# microz.net
KiCad netlist of a schematic drawn in Altium Designer
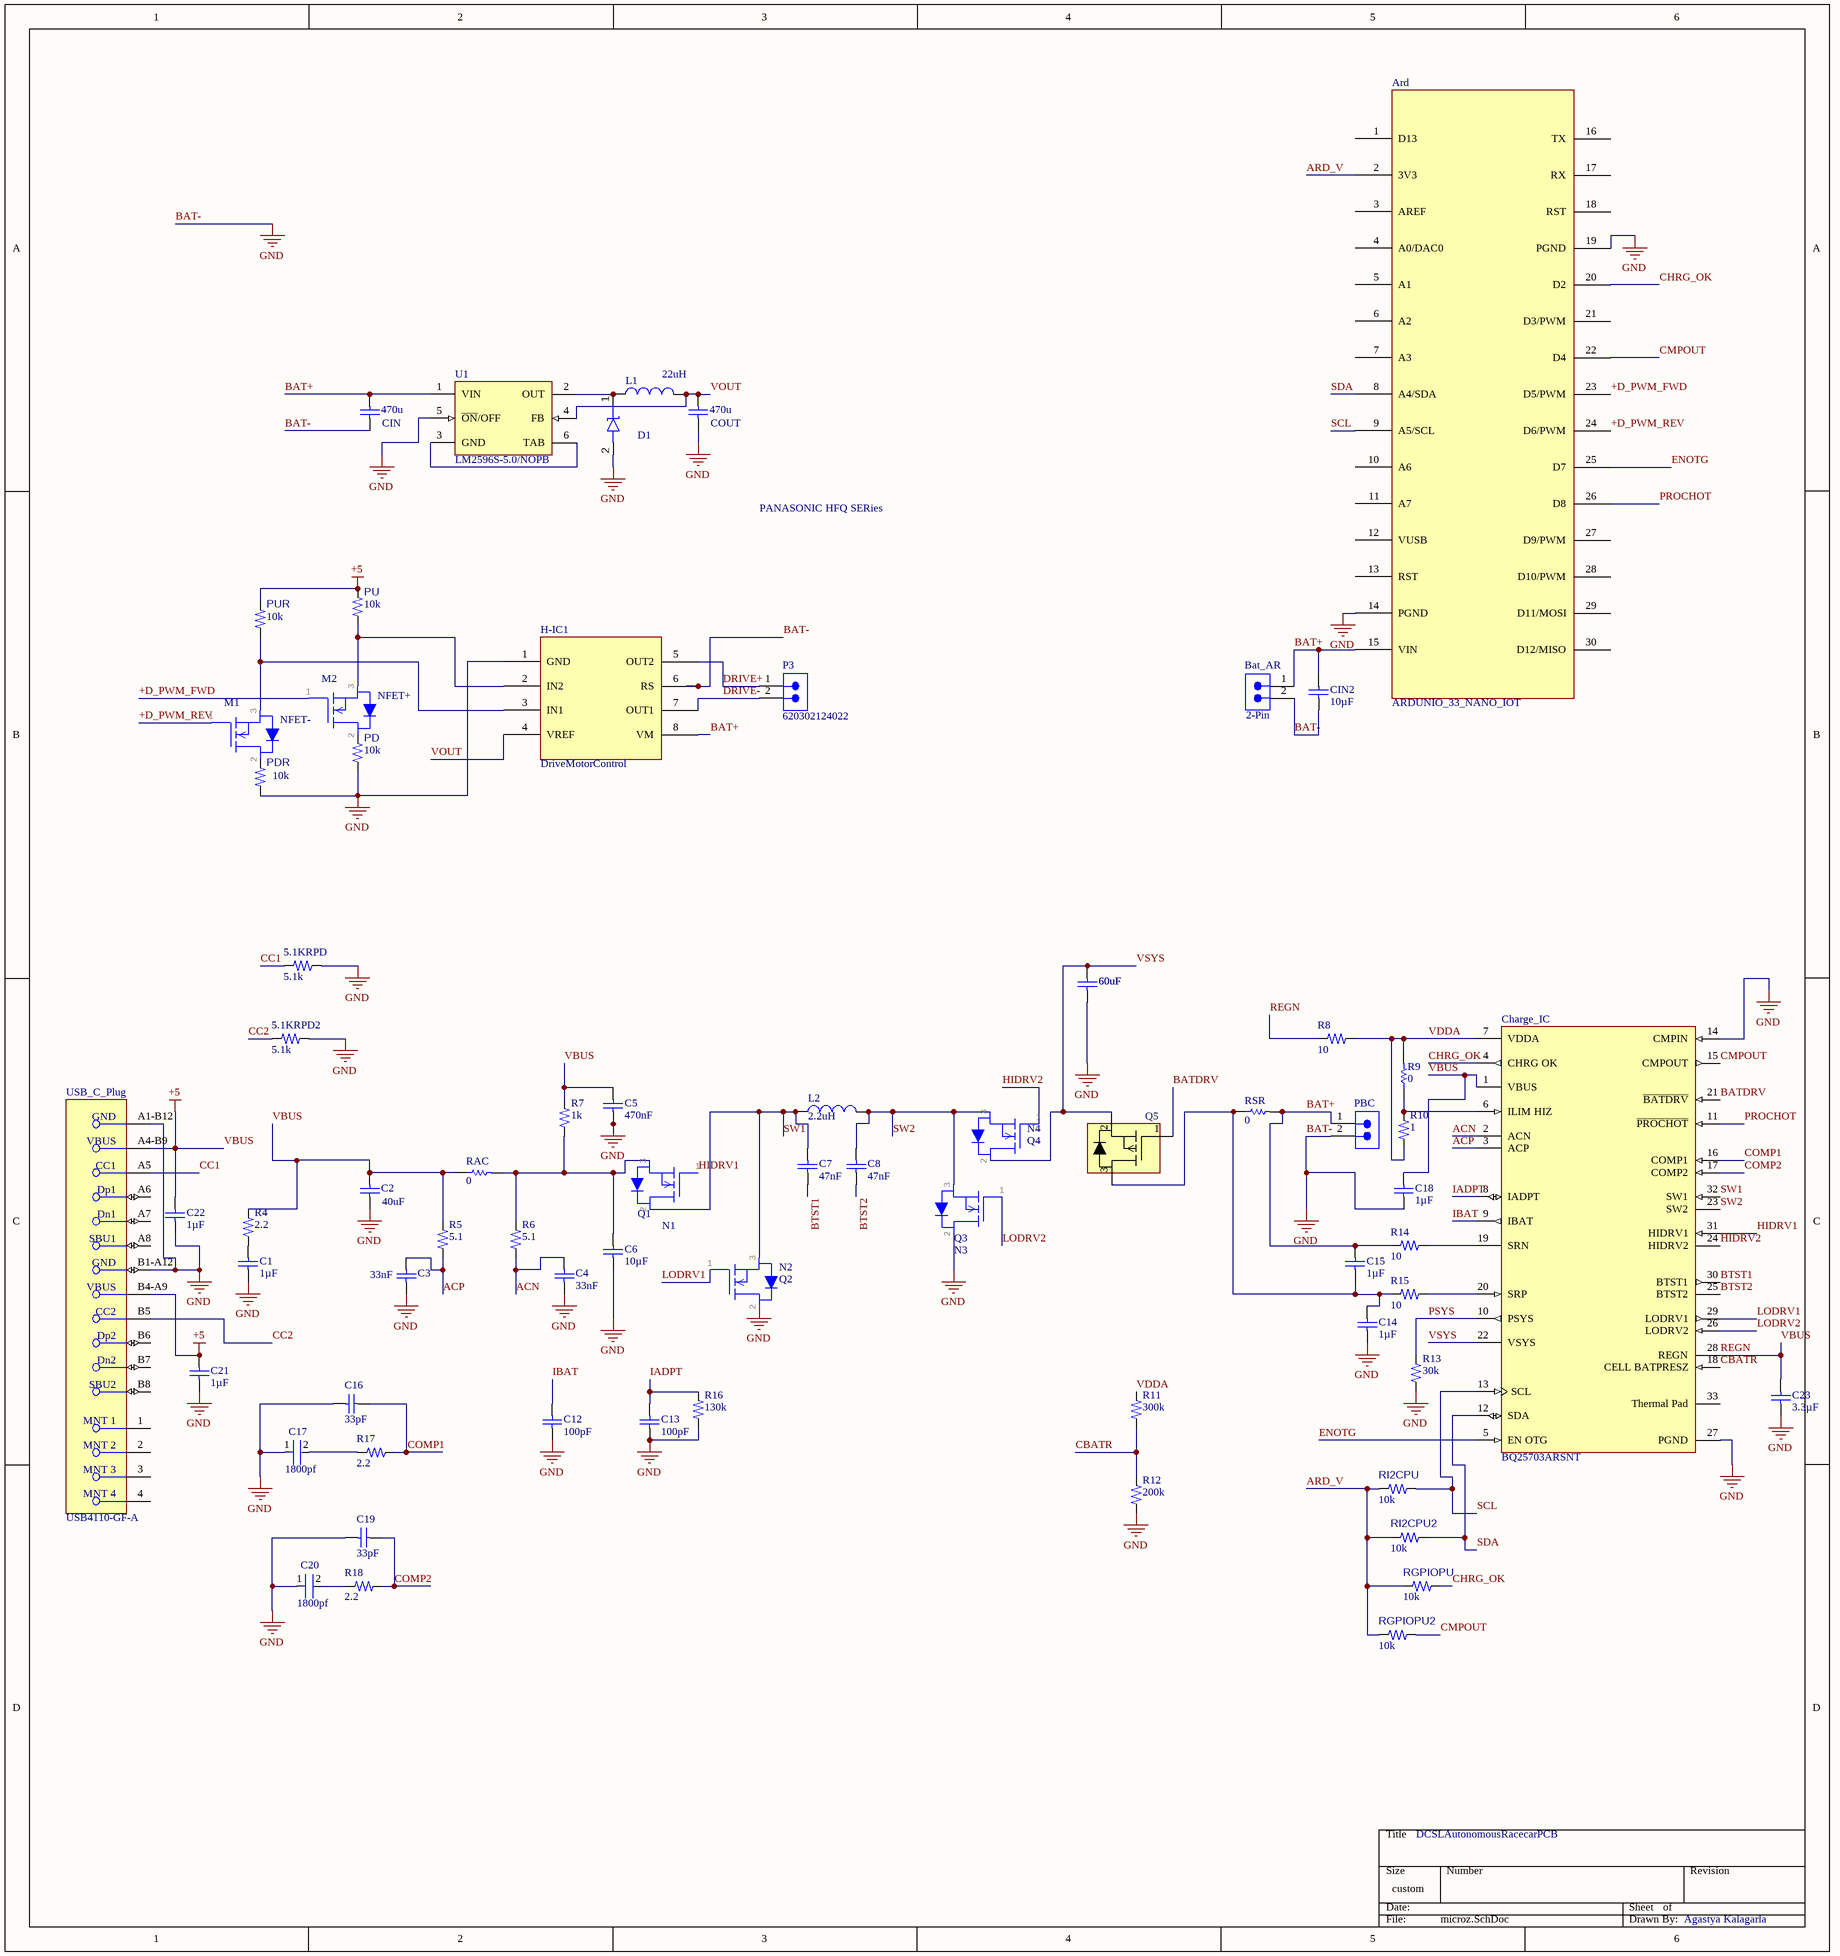
[diagram p0: microz.SchDoc]

(export (version "E")
  (design (tool "Eeschema 10.0.6"))
  (components
    (comp (ref "5.1KRPD")
      (value "5.1k")
      (footprint "RESC0603(1608)_L")
      (description "0603 (1608 Metric) 1/10 W 5K1 1 Precision Thick Film Chip Resistor")
      (fields (field (name "POWER") "100mW") (field (name "TOLERANCE") "0.1%"))
      (libsource (lib "Hytech Racing") (part "Resistor"))
    )
    (comp (ref "5.1KRPD2")
      (value "5.1k")
      (footprint "RESC0603(1608)_L")
      (description "0603 (1608 Metric) 1/10 W 5K1 1 Precision Thick Film Chip Resistor")
      (fields (field (name "POWER") "100mW") (field (name "TOLERANCE") "0.1%"))
      (libsource (lib "Hytech Racing") (part "Resistor"))
    )
    (comp (ref "60uF")
      (value "60uF")
      (footprint "RESC0603(1608)_L")
      (description "Imperial 0603 Capacitor")
      (fields (field (name "Comment") "0603-CAP"))
      (libsource (lib "Hytech Racing") (part "Capacitor-Ceramic"))
    )
    (comp (ref "Ard")
      (value "ARDUNIO_33_NANO_IOT")
      (footprint "Arduino33NanoIOT")
      (description "Arduino Nano IC for I2C Comms/Control")
      (libsource (lib "Schlib1") (part "ARDUNIO_33_NANO_IOT"))
    )
    (comp (ref "Bat_AR")
      (value "2-Pin")
      (footprint "620302124022")
      (libsource (lib "Altium Content Vault") (part "Header_Male_1R_02P"))
    )
    (comp (ref "C1")
      (value "1µF")
      (footprint "RESC0402(1005)_L")
      (description "Chip Capacitor, 1u 25V 0402 X7R")
      (fields (field (name "Comment") "Capacitor 1u"))
      (libsource (lib "Hytech Racing") (part "CAP-NP-2"))
    )
    (comp (ref "C2")
      (value "40uF")
      (footprint "RESC0603(1608)_L")
      (description "Imperial 0603 Capacitor")
      (fields (field (name "Comment") "0603-CAP"))
      (libsource (lib "Hytech Racing") (part "Capacitor-Ceramic"))
    )
    (comp (ref "C3")
      (value "33nF")
      (footprint "RESC0603(1608)_L")
      (description "Chip Capacitor, 33n 10V 0603 X7R")
      (fields (field (name "Comment") "Capacitor 33n"))
      (libsource (lib "Hytech Racing") (part "CAP-NP-2"))
    )
    (comp (ref "C4")
      (value "33nF")
      (footprint "RESC0603(1608)_L")
      (description "Chip Capacitor, 33n 10V 0603 X7R")
      (fields (field (name "Comment") "Capacitor 33n"))
      (libsource (lib "Hytech Racing") (part "CAP-NP-2"))
    )
    (comp (ref "C5")
      (value "470nF")
      (footprint "RESC0603(1608)_L")
      (description "Chip Capacitor, 470n 50V 0603 X7R")
      (fields (field (name "Comment") "Capacitor 470n"))
      (libsource (lib "Hytech Racing") (part "CAP-NP-2"))
    )
    (comp (ref "C6")
      (value "10µF")
      (footprint "RESC0805(2012)_L")
      (description "Chip Capacitor, 10u 25V 0805 X7R")
      (fields (field (name "Comment") "Capacitor 10u"))
      (libsource (lib "Hytech Racing") (part "CAP-NP-2"))
    )
    (comp (ref "C7")
      (value "47nF")
      (footprint "RESC0603(1608)_L")
      (description "Chip Capacitor, 47n 50V 0603 X7R")
      (fields (field (name "Comment") "Capacitor 47n"))
      (libsource (lib "Hytech Racing") (part "CAP-NP-2"))
    )
    (comp (ref "C8")
      (value "47nF")
      (footprint "RESC0603(1608)_L")
      (description "Chip Capacitor, 47n 50V 0603 X7R")
      (fields (field (name "Comment") "Capacitor 47n"))
      (libsource (lib "Hytech Racing") (part "CAP-NP-2"))
    )
    (comp (ref "C12")
      (value "100pF")
      (footprint "RESC0603(1608)_L")
      (description "Chip Capacitor, 100p 50V 0603 X7R")
      (fields (field (name "Comment") "Capacitor 100p"))
      (libsource (lib "Hytech Racing") (part "CAP-NP-2"))
    )
    (comp (ref "C13")
      (value "100pF")
      (footprint "RESC0603(1608)_L")
      (description "Chip Capacitor, 100p 50V 0603 X7R")
      (fields (field (name "Comment") "Capacitor 100p"))
      (libsource (lib "Hytech Racing") (part "CAP-NP-2"))
    )
    (comp (ref "C14")
      (value "1µF")
      (footprint "RESC0402(1005)_L")
      (description "Chip Capacitor, 1u 25V 0402 X7R")
      (fields (field (name "Comment") "Capacitor 1u"))
      (libsource (lib "Hytech Racing") (part "CAP-NP-2"))
    )
    (comp (ref "C15")
      (value "1µF")
      (footprint "RESC0402(1005)_L")
      (description "Chip Capacitor, 1u 25V 0402 X7R")
      (fields (field (name "Comment") "Capacitor 1u"))
      (libsource (lib "Hytech Racing") (part "CAP-NP-2"))
    )
    (comp (ref "C16")
      (value "33pF")
      (footprint "RESC0603(1608)_L")
      (description "Chip Capacitor, 33p 50V 0603 X7R")
      (fields (field (name "Comment") "Capacitor 33p"))
      (libsource (lib "Hytech Racing") (part "CAP-NP-2"))
    )
    (comp (ref "C17")
      (value "1800pf")
      (footprint "FP-GRM188-0_1-e0_2_0_5-IPC_A")
      (description "Chip Multilayer Ceramic Capacitors for General Purpose, 0603, 1800pF, C0G, 30ppm/°C, 5%, 50V")
      (fields (field (name "TOLERANCE") "5%") (field (name "VOLTAGE") "50V"))
      (libsource (lib "Altium Content Vault") (part "11868f565c42a9108669ba33697ecf6"))
    )
    (comp (ref "C18")
      (value "1µF")
      (footprint "RESC0402(1005)_L")
      (description "Chip Capacitor, 1u 25V 0402 X7R")
      (fields (field (name "Comment") "Capacitor 1u"))
      (libsource (lib "Hytech Racing") (part "CAP-NP-2"))
    )
    (comp (ref "C19")
      (value "33pF")
      (footprint "RESC0603(1608)_L")
      (description "Chip Capacitor, 33p 50V 0603 X7R")
      (fields (field (name "Comment") "Capacitor 33p"))
      (libsource (lib "Hytech Racing") (part "CAP-NP-2"))
    )
    (comp (ref "C20")
      (value "1800pf")
      (footprint "FP-GRM188-0_1-e0_2_0_5-IPC_A")
      (description "Chip Multilayer Ceramic Capacitors for General Purpose, 0603, 1800pF, C0G, 30ppm/°C, 5%, 50V")
      (fields (field (name "TOLERANCE") "5%") (field (name "VOLTAGE") "50V"))
      (libsource (lib "Altium Content Vault") (part "11868f565c42a9108669ba33697ecf6"))
    )
    (comp (ref "C21")
      (value "1µF")
      (footprint "RESC0402(1005)_L")
      (description "Chip Capacitor, 1u 25V 0402 X7R")
      (fields (field (name "Comment") "Capacitor 1u"))
      (libsource (lib "Hytech Racing") (part "CAP-NP-2"))
    )
    (comp (ref "C22")
      (value "1µF")
      (footprint "RESC0402(1005)_L")
      (description "Chip Capacitor, 1u 25V 0402 X7R")
      (fields (field (name "Comment") "Capacitor 1u"))
      (libsource (lib "Hytech Racing") (part "CAP-NP-2"))
    )
    (comp (ref "C23")
      (value "3.3µF")
      (footprint "RESC0603(1608)_L")
      (description "Chip Capacitor, 3u3 50V 0603 X7R")
      (fields (field (name "Comment") "Capacitor 3u3"))
      (libsource (lib "Hytech Racing") (part "CAP-NP-2"))
    )
    (comp (ref "Charge_IC")
      (value "BQ25703ARSNT")
      (footprint "FP-RSN0032B-MFG")
      (description "IC BATT MON MULTI-CHEM 32WQFN")
      (fields
        (field (name "OCTOPART") "https://octopart.com/bq25703arsnt-texas+instruments-81848930")
        (field (name "MANUFACTURER") "Texas Instruments")
      )
      (libsource (lib "Altium Content Vault") (part "15ddd9f6a7647243260becfffa45dc3"))
    )
    (comp (ref "CIN")
      (value "470u")
      (footprint "RESC0603(1608)_L")
      (description "Imperial 0603 Capacitor")
      (fields (field (name "Comment") "0603-CAP"))
      (libsource (lib "Hytech Racing") (part "Capacitor-Ceramic"))
    )
    (comp (ref "CIN2")
      (value "10µF")
      (footprint "RESC0805(2012)_L")
      (description "Chip Capacitor, 10u 50V 0805 X7R")
      (fields (field (name "Comment") "Capacitor 10u"))
      (libsource (lib "Hytech Racing") (part "CAP-NP-2"))
    )
    (comp (ref "COUT")
      (value "470u")
      (footprint "RESC0603(1608)_L")
      (description "Imperial 0603 Capacitor")
      (fields (field (name "Comment") "0603-CAP"))
      (libsource (lib "Hytech Racing") (part "Capacitor-Ceramic"))
    )
    (comp (ref "D1")
      (value "DIODE_SCHOTTKY_SOD-323")
      (footprint "SOD-323")
      (description "Schottky Diode with SOD-323 Footprint")
      (libsource (lib "Hytech Racing") (part "Schottky Diode"))
    )
    (comp (ref "H-IC1")
      (value "DriveMotorControl")
      (footprint "TB67H451FNG,EL")
      (description "H-Bridge IC")
      (libsource (lib "Schlib1") (part "DriveMotorControl"))
    )
    (comp (ref "L1")
      (value "22uH")
      (footprint "INDC3225X24N")
      (description "1210 Inductor")
      (libsource (lib "Hytech Racing") (part "IND_1210"))
    )
    (comp (ref "L2")
      (value "2.2uH")
      (footprint "INDC3225X24N")
      (description "1210 Inductor")
      (fields (field (name "Comment") "IND_1210"))
      (libsource (lib "Hytech Racing") (part "IND_1210"))
    )
    (comp (ref "N1")
      (value "Q1")
      (footprint "DPAK(2-7K1S)")
      (description "N Channel MOSFET, DPAK(2-7K1S) Footprint")
      (libsource (lib "Hytech Racing") (part "N Channel MOSFET"))
    )
    (comp (ref "N2")
      (value "Q2")
      (footprint "DPAK(2-7K1S)")
      (description "N Channel MOSFET, DPAK(2-7K1S) Footprint")
      (libsource (lib "Hytech Racing") (part "N Channel MOSFET"))
    )
    (comp (ref "N3")
      (value "Q3")
      (footprint "DPAK(2-7K1S)")
      (description "N Channel MOSFET, DPAK(2-7K1S) Footprint")
      (libsource (lib "Hytech Racing") (part "N Channel MOSFET"))
    )
    (comp (ref "N4")
      (value "Q4")
      (footprint "DPAK(2-7K1S)")
      (description "N Channel MOSFET, DPAK(2-7K1S) Footprint")
      (libsource (lib "Hytech Racing") (part "N Channel MOSFET"))
    )
    (comp (ref "NFET+")
      (value "M2")
      (footprint "DPAK(2-7K1S)")
      (description "N Channel MOSFET, DPAK(2-7K1S) Footprint")
      (libsource (lib "Hytech Racing") (part "N Channel MOSFET"))
    )
    (comp (ref "NFET-")
      (value "M1")
      (footprint "DPAK(2-7K1S)")
      (description "N Channel MOSFET, DPAK(2-7K1S) Footprint")
      (libsource (lib "Hytech Racing") (part "N Channel MOSFET"))
    )
    (comp (ref "P3")
      (value "620302124022")
      (footprint "620302124022")
      (libsource (lib "Altium Content Vault") (part "Header_Male_1R_02P"))
    )
    (comp (ref "PBC")
      (value "620302124022")
      (footprint "620302124022")
      (libsource (lib "Altium Content Vault") (part "Header_Male_1R_02P"))
    )
    (comp (ref "PD")
      (value "10k")
      (footprint "RESC0603(1608)_L")
      (description "0603 (1608 Metric) 1/10 W 10K 1 Precision Thick Film Chip Resistor")
      (fields (field (name "POWER") "100mW") (field (name "TOLERANCE") "0.1%"))
      (libsource (lib "Hytech Racing") (part "Resistor"))
    )
    (comp (ref "PDR")
      (value "10k")
      (footprint "RESC0603(1608)_L")
      (description "0603 (1608 Metric) 1/10 W 10K 1 Precision Thick Film Chip Resistor")
      (fields (field (name "POWER") "100mW") (field (name "TOLERANCE") "0.1%"))
      (libsource (lib "Hytech Racing") (part "Resistor"))
    )
    (comp (ref "PU")
      (value "10k")
      (footprint "RESC0603(1608)_L")
      (description "0603 (1608 Metric) 1/10 W 10K 1 Precision Thick Film Chip Resistor")
      (fields (field (name "POWER") "100mW") (field (name "TOLERANCE") "0.1%"))
      (libsource (lib "Hytech Racing") (part "Resistor"))
    )
    (comp (ref "PUR")
      (value "10k")
      (footprint "RESC0603(1608)_L")
      (description "0603 (1608 Metric) 1/10 W 10K 1 Precision Thick Film Chip Resistor")
      (fields (field (name "POWER") "100mW") (field (name "TOLERANCE") "0.1%"))
      (libsource (lib "Hytech Racing") (part "Resistor"))
    )
    (comp (ref "Q5")
      (value "DMP3056L-7")
      (footprint "SOT96P240X110-3N/SOT23-3")
      (description "P-MOSFET Enhancement Mode")
      (fields (field (name "MANUFACTURER") "Diodes Incorporated") (field (name "SOURCE") "LOGICFETS.SchLib"))
      (libsource (lib "Hytech Racing") (part "DMP3056L-7"))
    )
    (comp (ref "R4")
      (value "2.2")
      (footprint "RESC0603(1608)_L")
      (description "0603 (1608 Metric) 1/10 W 2R2 5 Thick Film Chip Resistor")
      (fields (field (name "POWER") "100mW") (field (name "TOLERANCE") "5%"))
      (libsource (lib "Hytech Racing") (part "Resistor"))
    )
    (comp (ref "R5")
      (value "5.1")
      (footprint "RESC0603(1608)_L")
      (description "0603 (1608 Metric) 1/10 W 5R1 5 Thick Film Chip Resistor")
      (fields (field (name "POWER") "100mW") (field (name "TOLERANCE") "5%"))
      (libsource (lib "Hytech Racing") (part "Resistor"))
    )
    (comp (ref "R6")
      (value "5.1")
      (footprint "RESC0603(1608)_L")
      (description "0603 (1608 Metric) 1/10 W 5R1 5 Thick Film Chip Resistor")
      (fields (field (name "POWER") "100mW") (field (name "TOLERANCE") "5%"))
      (libsource (lib "Hytech Racing") (part "Resistor"))
    )
    (comp (ref "R7")
      (value "1k")
      (footprint "RESC0603(1608)_L")
      (description "0603 (1608 Metric) 1/10 W 1K 1 Precision Thick Film Chip Resistor")
      (fields (field (name "TOLERANCE") "0.1%") (field (name "POWER") "100mW"))
      (libsource (lib "Hytech Racing") (part "Resistor"))
    )
    (comp (ref "R8")
      (value "10")
      (footprint "RESC0603(1608)_L")
      (description "0603 (1608 Metric) 1/10 W 10R 1 Precision Thick Film Chip Resistor")
      (fields (field (name "POWER") "100mW") (field (name "TOLERANCE") "0.1%"))
      (libsource (lib "Hytech Racing") (part "Resistor"))
    )
    (comp (ref "R9")
      (value "0")
      (footprint "RESC1005X40X25ML05T05")
      (description "Chip Resistor, 0 Ohm, 0.1 W, -55 to 155 degC, 0402 (1005 Metric)")
      (fields (field (name "TOLERANCE") "5%") (field (name "POWER") "100mW"))
      (libsource (lib "Hytech Racing") (part "RES-2"))
    )
    (comp (ref "R10")
      (value "1")
      (footprint "RESC0603(1608)_L")
      (description "0603 (1608 Metric) 1/10 W 1R 5 Thick Film Chip Resistor")
      (fields (field (name "POWER") "100mW") (field (name "TOLERANCE") "5%"))
      (libsource (lib "Hytech Racing") (part "Resistor"))
    )
    (comp (ref "R11")
      (value "300k")
      (footprint "RESC0603(1608)_L")
      (description "0603 (1608 Metric) 1/10 W 300K 1 Precision Thick Film Chip Resistor")
      (fields (field (name "POWER") "100mW") (field (name "TOLERANCE") "0.1%"))
      (libsource (lib "Hytech Racing") (part "Resistor"))
    )
    (comp (ref "R12")
      (value "200k")
      (footprint "RESC0603(1608)_L")
      (description "0603 (1608 Metric) 1/10 W 200K 1 Precision Thick Film Chip Resistor")
      (fields (field (name "TOLERANCE") "0.1%") (field (name "POWER") "100mW"))
      (libsource (lib "Hytech Racing") (part "Resistor"))
    )
    (comp (ref "R13")
      (value "30k")
      (footprint "RESC0603(1608)_L")
      (description "0603 (1608 Metric) 1/10 W 30K 1 Precision Thick Film Chip Resistor")
      (fields (field (name "TOLERANCE") "0.1%") (field (name "POWER") "100mW"))
      (libsource (lib "Hytech Racing") (part "Resistor"))
    )
    (comp (ref "R14")
      (value "10")
      (footprint "RESC0603(1608)_L")
      (description "0603 (1608 Metric) 1/10 W 10R 1 Precision Thick Film Chip Resistor")
      (fields (field (name "POWER") "100mW") (field (name "TOLERANCE") "0.1%"))
      (libsource (lib "Hytech Racing") (part "Resistor"))
    )
    (comp (ref "R15")
      (value "10")
      (footprint "RESC0603(1608)_L")
      (description "0603 (1608 Metric) 1/10 W 10R 1 Precision Thick Film Chip Resistor")
      (fields (field (name "POWER") "100mW") (field (name "TOLERANCE") "0.1%"))
      (libsource (lib "Hytech Racing") (part "Resistor"))
    )
    (comp (ref "R16")
      (value "130k")
      (footprint "RESC0603(1608)_L")
      (description "0603 (1608 Metric) 1/10 W 130K 1 Precision Thick Film Chip Resistor")
      (fields (field (name "POWER") "100mW") (field (name "TOLERANCE") "0.1%"))
      (libsource (lib "Hytech Racing") (part "Resistor"))
    )
    (comp (ref "R17")
      (value "2.2")
      (footprint "RESC0603(1608)_L")
      (description "0603 (1608 Metric) 1/10 W 2R2 5 Thick Film Chip Resistor")
      (fields (field (name "POWER") "100mW") (field (name "TOLERANCE") "5%"))
      (libsource (lib "") (part "Resistor_1"))
    )
    (comp (ref "R18")
      (value "2.2")
      (footprint "RESC0603(1608)_L")
      (description "0603 (1608 Metric) 1/10 W 2R2 5 Thick Film Chip Resistor")
      (fields (field (name "POWER") "100mW") (field (name "TOLERANCE") "5%"))
      (libsource (lib "") (part "Resistor_1"))
    )
    (comp (ref "RAC")
      (value "0")
      (footprint "RESC1005X40X25ML05T05")
      (description "Chip Resistor, 0 Ohm, 0.1 W, -55 to 155 degC, 0402 (1005 Metric)")
      (fields (field (name "TOLERANCE") "5%") (field (name "POWER") "100mW"))
      (libsource (lib "Hytech Racing") (part "RES-2"))
    )
    (comp (ref "RGPIOPU")
      (value "10k")
      (footprint "RESC0603(1608)_L")
      (description "0603 (1608 Metric) 1/10 W 10K 1 Precision Thick Film Chip Resistor")
      (fields (field (name "POWER") "100mW") (field (name "TOLERANCE") "0.1%"))
      (libsource (lib "Hytech Racing") (part "Resistor"))
    )
    (comp (ref "RGPIOPU2")
      (value "10k")
      (footprint "RESC0603(1608)_L")
      (description "0603 (1608 Metric) 1/10 W 10K 1 Precision Thick Film Chip Resistor")
      (fields (field (name "POWER") "100mW") (field (name "TOLERANCE") "0.1%"))
      (libsource (lib "Hytech Racing") (part "Resistor"))
    )
    (comp (ref "RI2CPU")
      (value "10k")
      (footprint "RESC0603(1608)_L")
      (description "0603 (1608 Metric) 1/10 W 10K 1 Precision Thick Film Chip Resistor")
      (fields (field (name "POWER") "100mW") (field (name "TOLERANCE") "0.1%"))
      (libsource (lib "Hytech Racing") (part "Resistor"))
    )
    (comp (ref "RI2CPU2")
      (value "10k")
      (footprint "RESC0603(1608)_L")
      (description "0603 (1608 Metric) 1/10 W 10K 1 Precision Thick Film Chip Resistor")
      (fields (field (name "POWER") "100mW") (field (name "TOLERANCE") "0.1%"))
      (libsource (lib "Hytech Racing") (part "Resistor"))
    )
    (comp (ref "RSR")
      (value "0")
      (footprint "RESC1005X40X25ML05T05")
      (description "Chip Resistor, 0 Ohm, 0.1 W, -55 to 155 degC, 0402 (1005 Metric)")
      (fields (field (name "TOLERANCE") "5%") (field (name "POWER") "100mW"))
      (libsource (lib "Hytech Racing") (part "RES-2"))
    )
    (comp (ref "U1")
      (value "LM2596S-5.0/NOPB")
      (footprint "KTT0005B_M")
      (description "SIMPLE SWITCHER® Power Converter 150 KHz 3A Step-Down Voltage Regulator, 5-pin TO-263, Pb-Free")
      (fields (field (name "MANUFACTURER") "Texas Instruments"))
      (libsource (lib "Altium Content Vault") (part "PM-REG-LM2575HVS-12"))
    )
    (comp (ref "USB_C_Plug")
      (value "USB4110-GF-A")
      (footprint "FP-USB4110-GF-A-MFG")
      (description "CONN USB 2.0 TYPE-C R/A SMT")
      (fields
        (field (name "OCTOPART") "https://octopart.com/usb4110-gf-a-gct-103941985")
        (field (name "MANUFACTURER") "GCT")
      )
      (libsource (lib "Altium Content Vault") (part "e23f2b38bb3c3f98e683ebab9ede730"))
    )
  )
  (nets
    (net (code "1") (name "+5") (class "Default")
      (node (ref "C18") (pin "2") (pinfunction "2_2") (pintype "passive"))
      (node (ref "C2") (pin "2") (pinfunction "2_2") (pintype "passive"))
      (node (ref "C21") (pin "2") (pinfunction "2_2") (pintype "passive"))
      (node (ref "C22") (pin "2") (pinfunction "2_2") (pintype "passive"))
      (node (ref "C23") (pin "2") (pinfunction "2_2") (pintype "passive"))
      (node (ref "C5") (pin "2") (pinfunction "2_2") (pintype "passive"))
      (node (ref "Charge_IC") (pin "1") (pinfunction "VBUS_1") (pintype "power_in"))
      (node (ref "Charge_IC") (pin "28") (pinfunction "REGN_28") (pintype "power_in"))
      (node (ref "PU") (pin "2") (pinfunction "2_2") (pintype "passive"))
      (node (ref "PUR") (pin "2") (pinfunction "2_2") (pintype "passive"))
      (node (ref "R4") (pin "2") (pinfunction "2_2") (pintype "passive"))
      (node (ref "R5") (pin "2") (pinfunction "2_2") (pintype "passive"))
      (node (ref "R7") (pin "2") (pinfunction "2_2") (pintype "passive"))
      (node (ref "R8") (pin "1") (pinfunction "1_1") (pintype "passive"))
      (node (ref "RAC") (pin "1") (pinfunction "1_1") (pintype "passive"))
      (node (ref "USB_C_Plug") (pin "A4-B9") (pinfunction "VBUS_A4-B9") (pintype "power_in"))
      (node (ref "USB_C_Plug") (pin "B4-A9") (pinfunction "VBUS_B4-A9") (pintype "power_in"))
    )
    (net (code "2") (name "/+D_PWM_FWD") (class "Default")
      (node (ref "Ard") (pin "23") (pinfunction "D5/PWM_23") (pintype "passive"))
      (node (ref "NFET+") (pin "1") (pinfunction "Gate_1") (pintype "passive"))
    )
    (net (code "3") (name "/+D_PWM_REV") (class "Default")
      (node (ref "Ard") (pin "24") (pinfunction "D6/PWM_24") (pintype "passive"))
      (node (ref "NFET-") (pin "1") (pinfunction "Gate_1") (pintype "passive"))
    )
    (net (code "4") (name "/ACN") (class "Default")
      (node (ref "C4") (pin "2") (pinfunction "2_2") (pintype "passive"))
      (node (ref "Charge_IC") (pin "2") (pinfunction "ACN_2") (pintype "power_in"))
      (node (ref "R6") (pin "1") (pinfunction "1_1") (pintype "passive"))
    )
    (net (code "5") (name "/ACP") (class "Default")
      (node (ref "C3") (pin "2") (pinfunction "2_2") (pintype "passive"))
      (node (ref "Charge_IC") (pin "3") (pinfunction "ACP_3") (pintype "power_in"))
      (node (ref "R5") (pin "1") (pinfunction "1_1") (pintype "passive"))
    )
    (net (code "6") (name "/ARD_V") (class "Default")
      (node (ref "Ard") (pin "2") (pinfunction "3V3_2") (pintype "passive"))
      (node (ref "RGPIOPU") (pin "1") (pinfunction "1_1") (pintype "passive"))
      (node (ref "RGPIOPU2") (pin "1") (pinfunction "1_1") (pintype "passive"))
      (node (ref "RI2CPU") (pin "1") (pinfunction "1_1") (pintype "passive"))
      (node (ref "RI2CPU2") (pin "1") (pinfunction "1_1") (pintype "passive"))
    )
    (net (code "7") (name "/BAT+") (class "Default")
      (node (ref "Ard") (pin "15") (pinfunction "VIN_15") (pintype "passive"))
      (node (ref "Bat_AR") (pin "1") (pinfunction "1_1") (pintype "passive"))
      (node (ref "C15") (pin "2") (pinfunction "2_2") (pintype "passive"))
      (node (ref "CIN") (pin "2") (pinfunction "2_2") (pintype "passive"))
      (node (ref "CIN2") (pin "2") (pinfunction "2_2") (pintype "passive"))
      (node (ref "H-IC1") (pin "8") (pinfunction "VM_8") (pintype "passive"))
      (node (ref "PBC") (pin "1") (pinfunction "1_1") (pintype "passive"))
      (node (ref "R14") (pin "1") (pinfunction "1_1") (pintype "passive"))
      (node (ref "RSR") (pin "2") (pinfunction "2_2") (pintype "passive"))
      (node (ref "U1") (pin "1") (pinfunction "VIN_1") (pintype "power_in"))
    )
    (net (code "8") (name "/BATDRV") (class "Default")
      (node (ref "Charge_IC") (pin "21") (pinfunction "~{BATDRV}_21") (pintype "input"))
      (node (ref "Q5") (pin "1") (pinfunction "G_1") (pintype "passive"))
    )
    (net (code "9") (name "/BTST1") (class "Default")
      (node (ref "C7") (pin "1") (pinfunction "1_1") (pintype "passive"))
      (node (ref "Charge_IC") (pin "30") (pinfunction "BTST1_30") (pintype "output"))
    )
    (net (code "10") (name "/BTST2") (class "Default")
      (node (ref "C8") (pin "1") (pinfunction "1_1") (pintype "passive"))
      (node (ref "Charge_IC") (pin "25") (pinfunction "BTST2_25") (pintype "power_in"))
    )
    (net (code "11") (name "/CBATR") (class "Default")
      (node (ref "Charge_IC") (pin "18") (pinfunction "CELL_BATPRESZ_18") (pintype "input"))
      (node (ref "R11") (pin "1") (pinfunction "1_1") (pintype "passive"))
      (node (ref "R12") (pin "2") (pinfunction "2_2") (pintype "passive"))
    )
    (net (code "12") (name "/CC1") (class "Default")
      (node (ref "5.1KRPD") (pin "1") (pinfunction "1_1") (pintype "passive"))
      (node (ref "USB_C_Plug") (pin "A5") (pinfunction "CC1_A5") (pintype "power_in"))
    )
    (net (code "13") (name "/CC2") (class "Default")
      (node (ref "5.1KRPD2") (pin "1") (pinfunction "1_1") (pintype "passive"))
      (node (ref "USB_C_Plug") (pin "B5") (pinfunction "CC2_B5") (pintype "power_in"))
    )
    (net (code "14") (name "/CHRG_OK") (class "Default")
      (node (ref "Ard") (pin "20") (pinfunction "D2_20") (pintype "passive"))
      (node (ref "Charge_IC") (pin "4") (pinfunction "CHRG_OK_4") (pintype "output"))
      (node (ref "RGPIOPU") (pin "2") (pinfunction "2_2") (pintype "passive"))
    )
    (net (code "15") (name "/CMPOUT") (class "Default")
      (node (ref "Ard") (pin "22") (pinfunction "D4_22") (pintype "passive"))
      (node (ref "Charge_IC") (pin "15") (pinfunction "CMPOUT_15") (pintype "output"))
      (node (ref "RGPIOPU2") (pin "2") (pinfunction "2_2") (pintype "passive"))
    )
    (net (code "16") (name "/COMP1") (class "Default")
      (node (ref "C16") (pin "2") (pinfunction "2_2") (pintype "passive"))
      (node (ref "Charge_IC") (pin "16") (pinfunction "COMP1_16") (pintype "input"))
      (node (ref "R17") (pin "1") (pinfunction "1_1") (pintype "passive"))
    )
    (net (code "17") (name "/COMP2") (class "Default")
      (node (ref "C19") (pin "2") (pinfunction "2_2") (pintype "passive"))
      (node (ref "Charge_IC") (pin "17") (pinfunction "COMP2_17") (pintype "input"))
      (node (ref "R18") (pin "1") (pinfunction "1_1") (pintype "passive"))
    )
    (net (code "18") (name "/DRIVE+") (class "Default")
      (node (ref "H-IC1") (pin "5") (pinfunction "OUT2_5") (pintype "passive"))
      (node (ref "P3") (pin "1") (pinfunction "1_1") (pintype "passive"))
    )
    (net (code "19") (name "/DRIVE-") (class "Default")
      (node (ref "H-IC1") (pin "7") (pinfunction "OUT1_7") (pintype "passive"))
      (node (ref "P3") (pin "2") (pinfunction "2_2") (pintype "passive"))
    )
    (net (code "20") (name "/ENOTG") (class "Default")
      (node (ref "Ard") (pin "25") (pinfunction "D7_25") (pintype "passive"))
      (node (ref "Charge_IC") (pin "5") (pinfunction "EN_OTG_5") (pintype "input"))
    )
    (net (code "21") (name "/HIDRV1") (class "Default")
      (node (ref "Charge_IC") (pin "31") (pinfunction "HIDRV1_31") (pintype "input"))
      (node (ref "N1") (pin "1") (pinfunction "Gate_1") (pintype "passive"))
    )
    (net (code "22") (name "/HIDRV2") (class "Default")
      (node (ref "Charge_IC") (pin "24") (pinfunction "HIDRV2_24") (pintype "power_in"))
      (node (ref "N4") (pin "1") (pinfunction "Gate_1") (pintype "passive"))
    )
    (net (code "23") (name "/IADPT") (class "Default")
      (node (ref "C13") (pin "2") (pinfunction "2_2") (pintype "passive"))
      (node (ref "Charge_IC") (pin "8") (pinfunction "IADPT_8") (pintype "bidirectional"))
      (node (ref "R16") (pin "2") (pinfunction "2_2") (pintype "passive"))
    )
    (net (code "24") (name "/IBAT") (class "Default")
      (node (ref "C12") (pin "2") (pinfunction "2_2") (pintype "passive"))
      (node (ref "Charge_IC") (pin "9") (pinfunction "IBAT_9") (pintype "output"))
    )
    (net (code "25") (name "/LODRV1") (class "Default")
      (node (ref "Charge_IC") (pin "29") (pinfunction "LODRV1_29") (pintype "output"))
      (node (ref "N2") (pin "1") (pinfunction "Gate_1") (pintype "passive"))
    )
    (net (code "26") (name "/LODRV2") (class "Default")
      (node (ref "Charge_IC") (pin "26") (pinfunction "LODRV2_26") (pintype "input"))
      (node (ref "N3") (pin "1") (pinfunction "Gate_1") (pintype "passive"))
    )
    (net (code "27") (name "/PROCHOT") (class "Default")
      (node (ref "Ard") (pin "26") (pinfunction "D8_26") (pintype "passive"))
      (node (ref "Charge_IC") (pin "11") (pinfunction "~{PROCHOT}_11") (pintype "input"))
    )
    (net (code "28") (name "/PSYS") (class "Default")
      (node (ref "Charge_IC") (pin "10") (pinfunction "PSYS_10") (pintype "output"))
      (node (ref "R13") (pin "2") (pinfunction "2_2") (pintype "passive"))
    )
    (net (code "29") (name "/SCL") (class "Default")
      (node (ref "Ard") (pin "9") (pinfunction "A5/SCL_9") (pintype "passive"))
      (node (ref "Charge_IC") (pin "13") (pinfunction "SCL_13") (pintype "input"))
      (node (ref "RI2CPU") (pin "2") (pinfunction "2_2") (pintype "passive"))
    )
    (net (code "30") (name "/SDA") (class "Default")
      (node (ref "Ard") (pin "8") (pinfunction "A4/SDA_8") (pintype "passive"))
      (node (ref "Charge_IC") (pin "12") (pinfunction "SDA_12") (pintype "bidirectional"))
      (node (ref "RI2CPU2") (pin "2") (pinfunction "2_2") (pintype "passive"))
    )
    (net (code "31") (name "/SW1") (class "Default")
      (node (ref "C7") (pin "2") (pinfunction "2_2") (pintype "passive"))
      (node (ref "Charge_IC") (pin "32") (pinfunction "SW1_32") (pintype "input"))
      (node (ref "L2") (pin "1") (pinfunction "1_1") (pintype "passive"))
      (node (ref "N1") (pin "2") (pinfunction "Drain_2") (pintype "passive"))
      (node (ref "N2") (pin "3") (pinfunction "Source_3") (pintype "passive"))
    )
    (net (code "32") (name "/SW2") (class "Default")
      (node (ref "C8") (pin "2") (pinfunction "2_2") (pintype "passive"))
      (node (ref "Charge_IC") (pin "23") (pinfunction "SW2_23") (pintype "power_in"))
      (node (ref "L2") (pin "2") (pinfunction "2_2") (pintype "passive"))
      (node (ref "N3") (pin "3") (pinfunction "Source_3") (pintype "passive"))
      (node (ref "N4") (pin "3") (pinfunction "Source_3") (pintype "passive"))
    )
    (net (code "33") (name "/VDDA") (class "Default")
      (node (ref "Charge_IC") (pin "7") (pinfunction "VDDA_7") (pintype "power_in"))
      (node (ref "R10") (pin "1") (pinfunction "1_1") (pintype "passive"))
      (node (ref "R11") (pin "2") (pinfunction "2_2") (pintype "passive"))
      (node (ref "R8") (pin "2") (pinfunction "2_2") (pintype "passive"))
      (node (ref "R9") (pin "2") (pinfunction "2_2") (pintype "passive"))
    )
    (net (code "34") (name "/VOUT") (class "Default")
      (node (ref "COUT") (pin "2") (pinfunction "2_2") (pintype "passive"))
      (node (ref "H-IC1") (pin "4") (pinfunction "VREF_4") (pintype "passive"))
      (node (ref "L1") (pin "2") (pinfunction "2_2") (pintype "passive"))
      (node (ref "U1") (pin "4") (pinfunction "FB_4") (pintype "input"))
    )
    (net (code "35") (name "/VSYS") (class "Default")
      (node (ref "60uF") (pin "2") (pinfunction "2_2") (pintype "passive"))
      (node (ref "Charge_IC") (pin "22") (pinfunction "VSYS_22") (pintype "power_in"))
      (node (ref "N4") (pin "2") (pinfunction "Drain_2") (pintype "passive"))
      (node (ref "Q5") (pin "2") (pinfunction "S_2") (pintype "passive"))
    )
    (net (code "36") (name "GND") (class "Default")
      (node (ref "5.1KRPD") (pin "2") (pinfunction "2_2") (pintype "passive"))
      (node (ref "5.1KRPD2") (pin "2") (pinfunction "2_2") (pintype "passive"))
      (node (ref "60uF") (pin "1") (pinfunction "1_1") (pintype "passive"))
      (node (ref "Ard") (pin "14") (pinfunction "PGND_14") (pintype "passive"))
      (node (ref "Ard") (pin "19") (pinfunction "PGND_19") (pintype "passive"))
      (node (ref "Bat_AR") (pin "2") (pinfunction "2_2") (pintype "passive"))
      (node (ref "C1") (pin "1") (pinfunction "1_1") (pintype "passive"))
      (node (ref "C12") (pin "1") (pinfunction "1_1") (pintype "passive"))
      (node (ref "C13") (pin "1") (pinfunction "1_1") (pintype "passive"))
      (node (ref "C14") (pin "1") (pinfunction "1_1") (pintype "passive"))
      (node (ref "C16") (pin "1") (pinfunction "1_1") (pintype "passive"))
      (node (ref "C17") (pin "1") (pinfunction "1_1") (pintype "passive"))
      (node (ref "C18") (pin "1") (pinfunction "1_1") (pintype "passive"))
      (node (ref "C19") (pin "1") (pinfunction "1_1") (pintype "passive"))
      (node (ref "C2") (pin "1") (pinfunction "1_1") (pintype "passive"))
      (node (ref "C20") (pin "1") (pinfunction "1_1") (pintype "passive"))
      (node (ref "C21") (pin "1") (pinfunction "1_1") (pintype "passive"))
      (node (ref "C22") (pin "1") (pinfunction "1_1") (pintype "passive"))
      (node (ref "C23") (pin "1") (pinfunction "1_1") (pintype "passive"))
      (node (ref "C3") (pin "1") (pinfunction "1_1") (pintype "passive"))
      (node (ref "C4") (pin "1") (pinfunction "1_1") (pintype "passive"))
      (node (ref "C5") (pin "1") (pinfunction "1_1") (pintype "passive"))
      (node (ref "C6") (pin "1") (pinfunction "1_1") (pintype "passive"))
      (node (ref "CIN") (pin "1") (pinfunction "1_1") (pintype "passive"))
      (node (ref "CIN2") (pin "1") (pinfunction "1_1") (pintype "passive"))
      (node (ref "COUT") (pin "1") (pinfunction "1_1") (pintype "passive"))
      (node (ref "Charge_IC") (pin "14") (pinfunction "CMPIN_14") (pintype "input"))
      (node (ref "Charge_IC") (pin "27") (pinfunction "PGND_27") (pintype "power_in"))
      (node (ref "D1") (pin "2") (pinfunction "A_2") (pintype "passive"))
      (node (ref "H-IC1") (pin "1") (pinfunction "GND_1") (pintype "passive"))
      (node (ref "H-IC1") (pin "6") (pinfunction "RS_6") (pintype "passive"))
      (node (ref "N2") (pin "2") (pinfunction "Drain_2") (pintype "passive"))
      (node (ref "N3") (pin "2") (pinfunction "Drain_2") (pintype "passive"))
      (node (ref "PBC") (pin "2") (pinfunction "2_2") (pintype "passive"))
      (node (ref "PD") (pin "1") (pinfunction "1_1") (pintype "passive"))
      (node (ref "PDR") (pin "1") (pinfunction "1_1") (pintype "passive"))
      (node (ref "R12") (pin "1") (pinfunction "1_1") (pintype "passive"))
      (node (ref "R13") (pin "1") (pinfunction "1_1") (pintype "passive"))
      (node (ref "R16") (pin "1") (pinfunction "1_1") (pintype "passive"))
      (node (ref "U1") (pin "5") (pinfunction "~{ON}/OFF_5") (pintype "input"))
      (node (ref "USB_C_Plug") (pin "A1-B12") (pinfunction "GND_A1-B12") (pintype "passive"))
      (node (ref "USB_C_Plug") (pin "B1-A12") (pinfunction "GND_B1-A12") (pintype "bidirectional"))
    )
    (net (code "37") (name "Net-(C1-Pad2)") (class "Default")
      (node (ref "C1") (pin "2") (pinfunction "2_2") (pintype "passive"))
      (node (ref "R4") (pin "1") (pinfunction "1_1") (pintype "passive"))
    )
    (net (code "38") (name "Net-(C17-Pad2)") (class "Default")
      (node (ref "C17") (pin "2") (pinfunction "2_2") (pintype "passive"))
      (node (ref "R17") (pin "2") (pinfunction "2_2") (pintype "passive"))
    )
    (net (code "39") (name "Net-(C20-Pad2)") (class "Default")
      (node (ref "C20") (pin "2") (pinfunction "2_2") (pintype "passive"))
      (node (ref "R18") (pin "2") (pinfunction "2_2") (pintype "passive"))
    )
    (net (code "40") (name "Net-(Charge_IC-ILIM_HIZ)") (class "Default")
      (node (ref "Charge_IC") (pin "6") (pinfunction "ILIM_HIZ_6") (pintype "input"))
      (node (ref "R10") (pin "2") (pinfunction "2_2") (pintype "passive"))
      (node (ref "R9") (pin "1") (pinfunction "1_1") (pintype "passive"))
    )
    (net (code "41") (name "Net-(Charge_IC-SRN)") (class "Default")
      (node (ref "Charge_IC") (pin "19") (pinfunction "SRN_19") (pintype "power_in"))
      (node (ref "R14") (pin "2") (pinfunction "2_2") (pintype "passive"))
    )
    (net (code "42") (name "Net-(Charge_IC-SRP)") (class "Default")
      (node (ref "Charge_IC") (pin "20") (pinfunction "SRP_20") (pintype "input"))
      (node (ref "R15") (pin "2") (pinfunction "2_2") (pintype "passive"))
    )
    (net (code "43") (name "Net-(D1-K)") (class "Default")
      (node (ref "D1") (pin "1") (pinfunction "K_1") (pintype "passive"))
      (node (ref "L1") (pin "1") (pinfunction "1_1") (pintype "passive"))
      (node (ref "U1") (pin "2") (pinfunction "OUT_2") (pintype "power_in"))
    )
    (net (code "44") (name "Net-(H-IC1-IN1)") (class "Default")
      (node (ref "H-IC1") (pin "3") (pinfunction "IN1_3") (pintype "passive"))
      (node (ref "NFET-") (pin "3") (pinfunction "Source_3") (pintype "passive"))
      (node (ref "PUR") (pin "1") (pinfunction "1_1") (pintype "passive"))
    )
    (net (code "45") (name "Net-(H-IC1-IN2)") (class "Default")
      (node (ref "H-IC1") (pin "2") (pinfunction "IN2_2") (pintype "passive"))
      (node (ref "NFET+") (pin "3") (pinfunction "Source_3") (pintype "passive"))
      (node (ref "PU") (pin "1") (pinfunction "1_1") (pintype "passive"))
    )
    (net (code "46") (name "Net-(N1-Source)") (class "Default")
      (node (ref "C6") (pin "2") (pinfunction "2_2") (pintype "passive"))
      (node (ref "N1") (pin "3") (pinfunction "Source_3") (pintype "passive"))
      (node (ref "R6") (pin "2") (pinfunction "2_2") (pintype "passive"))
      (node (ref "R7") (pin "1") (pinfunction "1_1") (pintype "passive"))
      (node (ref "RAC") (pin "2") (pinfunction "2_2") (pintype "passive"))
    )
    (net (code "47") (name "Net-(NFET+-Drain)") (class "Default")
      (node (ref "NFET+") (pin "2") (pinfunction "Drain_2") (pintype "passive"))
      (node (ref "PD") (pin "2") (pinfunction "2_2") (pintype "passive"))
    )
    (net (code "48") (name "Net-(NFET--Drain)") (class "Default")
      (node (ref "NFET-") (pin "2") (pinfunction "Drain_2") (pintype "passive"))
      (node (ref "PDR") (pin "2") (pinfunction "2_2") (pintype "passive"))
    )
    (net (code "49") (name "Net-(Q5-D)") (class "Default")
      (node (ref "C14") (pin "2") (pinfunction "2_2") (pintype "passive"))
      (node (ref "C15") (pin "1") (pinfunction "1_1") (pintype "passive"))
      (node (ref "Q5") (pin "3") (pinfunction "D_3") (pintype "passive"))
      (node (ref "R15") (pin "1") (pinfunction "1_1") (pintype "passive"))
      (node (ref "RSR") (pin "1") (pinfunction "1_1") (pintype "passive"))
    )
    (net (code "50") (name "Net-(U1-GND)") (class "Default")
      (node (ref "U1") (pin "3") (pinfunction "GND_3") (pintype "power_in"))
      (node (ref "U1") (pin "6") (pinfunction "TAB_6") (pintype "power_in"))
    )
    (net (code "51") (name "unconnected-(Ard-A0{slash}DAC0-Pad4)") (class "Default")
      (node (ref "Ard") (pin "4") (pinfunction "A0/DAC0_4") (pintype "passive"))
    )
    (net (code "52") (name "unconnected-(Ard-A1-Pad5)") (class "Default")
      (node (ref "Ard") (pin "5") (pinfunction "A1_5") (pintype "passive"))
    )
    (net (code "53") (name "unconnected-(Ard-A2-Pad6)") (class "Default")
      (node (ref "Ard") (pin "6") (pinfunction "A2_6") (pintype "passive"))
    )
    (net (code "54") (name "unconnected-(Ard-A3-Pad7)") (class "Default")
      (node (ref "Ard") (pin "7") (pinfunction "A3_7") (pintype "passive"))
    )
    (net (code "55") (name "unconnected-(Ard-A6-Pad10)") (class "Default")
      (node (ref "Ard") (pin "10") (pinfunction "A6_10") (pintype "passive"))
    )
    (net (code "56") (name "unconnected-(Ard-A7-Pad11)") (class "Default")
      (node (ref "Ard") (pin "11") (pinfunction "A7_11") (pintype "passive"))
    )
    (net (code "57") (name "unconnected-(Ard-AREF-Pad3)") (class "Default")
      (node (ref "Ard") (pin "3") (pinfunction "AREF_3") (pintype "passive"))
    )
    (net (code "58") (name "unconnected-(Ard-D3{slash}PWM-Pad21)") (class "Default")
      (node (ref "Ard") (pin "21") (pinfunction "D3/PWM_21") (pintype "passive"))
    )
    (net (code "59") (name "unconnected-(Ard-D9{slash}PWM-Pad27)") (class "Default")
      (node (ref "Ard") (pin "27") (pinfunction "D9/PWM_27") (pintype "passive"))
    )
    (net (code "60") (name "unconnected-(Ard-D10{slash}PWM-Pad28)") (class "Default")
      (node (ref "Ard") (pin "28") (pinfunction "D10/PWM_28") (pintype "passive"))
    )
    (net (code "61") (name "unconnected-(Ard-D11{slash}MOSI-Pad29)") (class "Default")
      (node (ref "Ard") (pin "29") (pinfunction "D11/MOSI_29") (pintype "passive"))
    )
    (net (code "62") (name "unconnected-(Ard-D12{slash}MISO-Pad30)") (class "Default")
      (node (ref "Ard") (pin "30") (pinfunction "D12/MISO_30") (pintype "passive"))
    )
    (net (code "63") (name "unconnected-(Ard-D13-Pad1)") (class "Default")
      (node (ref "Ard") (pin "1") (pinfunction "D13_1") (pintype "passive"))
    )
    (net (code "64") (name "unconnected-(Ard-RST-Pad13)") (class "Default")
      (node (ref "Ard") (pin "13") (pinfunction "RST_13") (pintype "passive"))
    )
    (net (code "65") (name "unconnected-(Ard-RST-Pad18)") (class "Default")
      (node (ref "Ard") (pin "18") (pinfunction "RST_18") (pintype "passive"))
    )
    (net (code "66") (name "unconnected-(Ard-RX-Pad17)") (class "Default")
      (node (ref "Ard") (pin "17") (pinfunction "RX_17") (pintype "passive"))
    )
    (net (code "67") (name "unconnected-(Ard-TX-Pad16)") (class "Default")
      (node (ref "Ard") (pin "16") (pinfunction "TX_16") (pintype "passive"))
    )
    (net (code "68") (name "unconnected-(Ard-VUSB-Pad12)") (class "Default")
      (node (ref "Ard") (pin "12") (pinfunction "VUSB_12") (pintype "passive"))
    )
    (net (code "69") (name "unconnected-(Charge_IC-Thermal_Pad-Pad33)") (class "Default")
      (node (ref "Charge_IC") (pin "33") (pinfunction "Thermal_Pad_33") (pintype "power_in"))
    )
    (net (code "70") (name "unconnected-(USB_C_Plug-Dn1-PadA7)") (class "Default")
      (node (ref "USB_C_Plug") (pin "A7") (pinfunction "Dn1_A7") (pintype "bidirectional"))
    )
    (net (code "71") (name "unconnected-(USB_C_Plug-Dn2-PadB7)") (class "Default")
      (node (ref "USB_C_Plug") (pin "B7") (pinfunction "Dn2_B7") (pintype "bidirectional"))
    )
    (net (code "72") (name "unconnected-(USB_C_Plug-Dp1-PadA6)") (class "Default")
      (node (ref "USB_C_Plug") (pin "A6") (pinfunction "Dp1_A6") (pintype "bidirectional"))
    )
    (net (code "73") (name "unconnected-(USB_C_Plug-Dp2-PadB6)") (class "Default")
      (node (ref "USB_C_Plug") (pin "B6") (pinfunction "Dp2_B6") (pintype "bidirectional"))
    )
    (net (code "74") (name "unconnected-(USB_C_Plug-MNT_1-Pad1)") (class "Default")
      (node (ref "USB_C_Plug") (pin "1") (pinfunction "MNT_1_1") (pintype "passive"))
    )
    (net (code "75") (name "unconnected-(USB_C_Plug-MNT_2-Pad2)") (class "Default")
      (node (ref "USB_C_Plug") (pin "2") (pinfunction "MNT_2_2") (pintype "passive"))
    )
    (net (code "76") (name "unconnected-(USB_C_Plug-MNT_3-Pad3)") (class "Default")
      (node (ref "USB_C_Plug") (pin "3") (pinfunction "MNT_3_3") (pintype "passive"))
    )
    (net (code "77") (name "unconnected-(USB_C_Plug-MNT_4-Pad4)") (class "Default")
      (node (ref "USB_C_Plug") (pin "4") (pinfunction "MNT_4_4") (pintype "passive"))
    )
    (net (code "78") (name "unconnected-(USB_C_Plug-SBU1-PadA8)") (class "Default")
      (node (ref "USB_C_Plug") (pin "A8") (pinfunction "SBU1_A8") (pintype "bidirectional"))
    )
    (net (code "79") (name "unconnected-(USB_C_Plug-SBU2-PadB8)") (class "Default")
      (node (ref "USB_C_Plug") (pin "B8") (pinfunction "SBU2_B8") (pintype "bidirectional"))
    )
  )
)
